# STM.net
KiCad netlist of a schematic drawn in Altium Designer
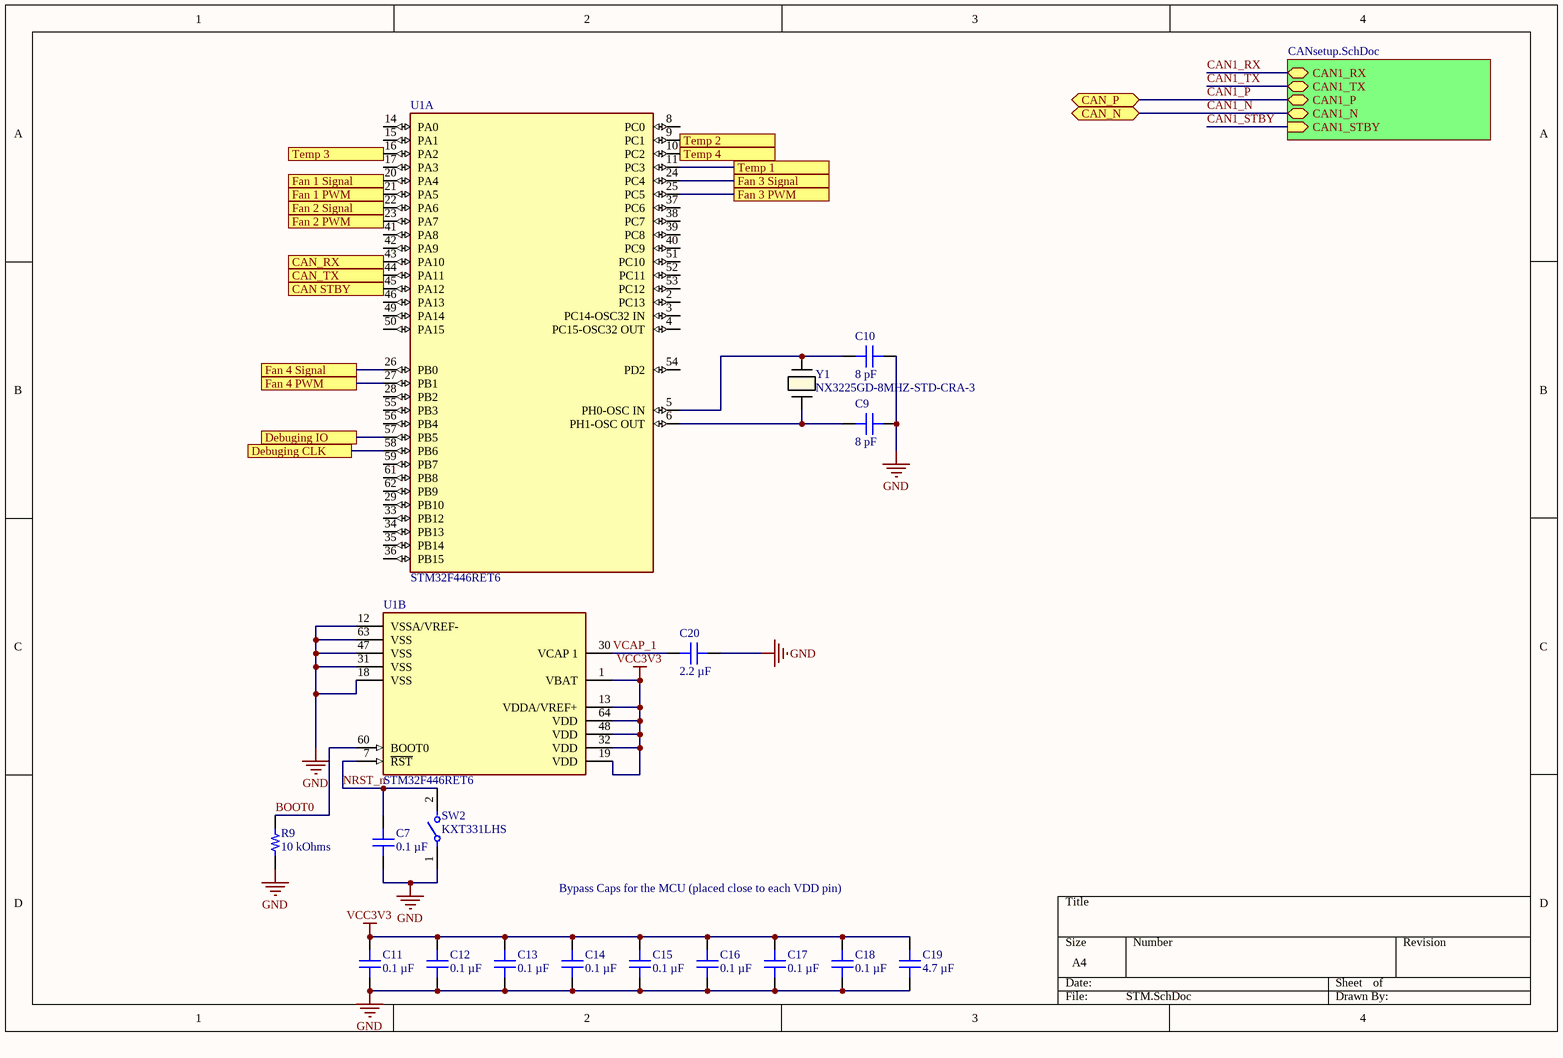
[diagram p0: STM.SchDoc]

(export (version "E")
  (design (tool "Eeschema 10.0.6"))
  (components
    (comp (ref "C7")
      (value "0.1 µF")
      (footprint "CAP 01005_0402")
      (description "CAP CER 0.1UF 6.3V X5R 01005")
      (fields
        (field (name "PART NUMBER") "CL02A104KQ2NNNC")
        (field (name "MANUFACTURER") "Samsung Electro-Mechanics")
      )
      (libsource (lib "Celestial Altium Library - altium_library") (part "Capacitor"))
    )
    (comp (ref "C9")
      (value "8 pF")
      (footprint "CAP 0402_1005")
      (description "CAP CER 8PF 50V C0G/NP0 0402")
      (fields
        (field (name "PART NUMBER") "GCM1555C1H8R0FA16D")
        (field (name "MANUFACTURER") "Murata Electronics")
      )
      (libsource (lib "Celestial Altium Library - altium_library") (part "Capacitor"))
    )
    (comp (ref "C10")
      (value "8 pF")
      (footprint "CAP 0402_1005")
      (description "CAP CER 8PF 50V C0G/NP0 0402")
      (fields
        (field (name "PART NUMBER") "GCM1555C1H8R0FA16D")
        (field (name "MANUFACTURER") "Murata Electronics")
      )
      (libsource (lib "Celestial Altium Library - altium_library") (part "Capacitor"))
    )
    (comp (ref "C11")
      (value "0.1 µF")
      (footprint "CAP 01005_0402")
      (description "CAP CER 0.1UF 6.3V X5R 01005")
      (fields
        (field (name "PART NUMBER") "CL02A104KQ2NNNC")
        (field (name "MANUFACTURER") "Samsung Electro-Mechanics")
      )
      (libsource (lib "Celestial Altium Library - altium_library") (part "Capacitor"))
    )
    (comp (ref "C12")
      (value "0.1 µF")
      (footprint "CAP 01005_0402")
      (description "CAP CER 0.1UF 6.3V X5R 01005")
      (fields
        (field (name "PART NUMBER") "CL02A104KQ2NNNC")
        (field (name "MANUFACTURER") "Samsung Electro-Mechanics")
      )
      (libsource (lib "Celestial Altium Library - altium_library") (part "Capacitor"))
    )
    (comp (ref "C13")
      (value "0.1 µF")
      (footprint "CAP 01005_0402")
      (description "CAP CER 0.1UF 6.3V X5R 01005")
      (fields
        (field (name "PART NUMBER") "CL02A104KQ2NNNC")
        (field (name "MANUFACTURER") "Samsung Electro-Mechanics")
      )
      (libsource (lib "Celestial Altium Library - altium_library") (part "Capacitor"))
    )
    (comp (ref "C14")
      (value "0.1 µF")
      (footprint "CAP 01005_0402")
      (description "CAP CER 0.1UF 6.3V X5R 01005")
      (fields
        (field (name "PART NUMBER") "CL02A104KQ2NNNC")
        (field (name "MANUFACTURER") "Samsung Electro-Mechanics")
      )
      (libsource (lib "Celestial Altium Library - altium_library") (part "Capacitor"))
    )
    (comp (ref "C15")
      (value "0.1 µF")
      (footprint "CAP 01005_0402")
      (description "CAP CER 0.1UF 6.3V X5R 01005")
      (fields
        (field (name "PART NUMBER") "CL02A104KQ2NNNC")
        (field (name "MANUFACTURER") "Samsung Electro-Mechanics")
      )
      (libsource (lib "Celestial Altium Library - altium_library") (part "Capacitor"))
    )
    (comp (ref "C16")
      (value "0.1 µF")
      (footprint "CAP 01005_0402")
      (description "CAP CER 0.1UF 6.3V X5R 01005")
      (fields
        (field (name "PART NUMBER") "CL02A104KQ2NNNC")
        (field (name "MANUFACTURER") "Samsung Electro-Mechanics")
      )
      (libsource (lib "Celestial Altium Library - altium_library") (part "Capacitor"))
    )
    (comp (ref "C17")
      (value "0.1 µF")
      (footprint "CAP 01005_0402")
      (description "CAP CER 0.1UF 6.3V X5R 01005")
      (fields
        (field (name "PART NUMBER") "CL02A104KQ2NNNC")
        (field (name "MANUFACTURER") "Samsung Electro-Mechanics")
      )
      (libsource (lib "Celestial Altium Library - altium_library") (part "Capacitor"))
    )
    (comp (ref "C18")
      (value "0.1 µF")
      (footprint "CAP 01005_0402")
      (description "CAP CER 0.1UF 6.3V X5R 01005")
      (fields
        (field (name "PART NUMBER") "CL02A104KQ2NNNC")
        (field (name "MANUFACTURER") "Samsung Electro-Mechanics")
      )
      (libsource (lib "Celestial Altium Library - altium_library") (part "Capacitor"))
    )
    (comp (ref "C19")
      (value "4.7 µF")
      (footprint "CAP 0402_1005")
      (description "CAP CER 4.7UF 16V X5R 0402")
      (fields
        (field (name "PART NUMBER") "CL05A475MO5NUNC")
        (field (name "MANUFACTURER") "Samsung Electro-Mechanics")
      )
      (libsource (lib "Celestial Altium Library - altium_library") (part "Capacitor"))
    )
    (comp (ref "C20")
      (value "2.2 µF")
      (footprint "CAP 0402_1005")
      (description "CAP CER 2.2UF 16V X5R 0402")
      (fields
        (field (name "PART NUMBER") "CL05A225KO5NQNC")
        (field (name "MANUFACTURER") "Samsung Electro-Mechanics")
      )
      (libsource (lib "Celestial Altium Library - altium_library") (part "Capacitor"))
    )
    (comp (ref "R9")
      (value "10 kOhms")
      (footprint "RES 0201_0603")
      (description "RES SMD 10K OHM 1% 1/20W 0201")
      (fields (field (name "PART NUMBER") "CRCW020110K0FKED") (field (name "MANUFACTURER") "Vishay Dale"))
      (libsource (lib "Celestial Altium Library - altium_library") (part "Resistor"))
    )
    (comp (ref "SW2")
      (value "KXT331LHS")
      (footprint "FP-KXT331LHS-MFG")
      (description "SWITCH TACTILE SPST-NO 0.02A 15V")
      (libsource (lib "Altium Content Vault") (part "bb27bde45df87f1f469753f287ef5ae"))
    )
    (comp (ref "U1")
      (value "STM32F446RET6")
      (footprint "FP-LQFP64-5W-MFG")
      (description "IC MCU 32BIT 512KB FLASH 64LQFP")
      (fields
        (field (name "OCTOPART") "https://octopart.com/stm32f446ret6-stmicroelectronics-52642920")
        (field (name "MANUFACTURER") "ST")
      )
      (libsource (lib "") (part "ee11adc32c0ab33b933cccf4348c338_1"))
    )
    (comp (ref "Y1")
      (value "NX3225GD-8MHZ-STD-CRA-3")
      (footprint "XTAL_NX3225GD-8MHZ-STD-CRA-3_NDK")
      (description "No Description Available")
      (fields (field (name "COPYRIGHT") "Copyright (C) 2024 Ultra Librarian. All rights reserved."))
      (libsource (lib "NX3225GD-8MHZ-STD-CRA-3") (part "NX3225GD-8MHZ-STD-CRA-3"))
    )
  )
  (nets
    (net (code "1") (name "/BOOT0") (class "Default")
      (node (ref "R9") (pin "2") (pinfunction "2_2") (pintype "passive"))
      (node (ref "U1") (pin "60") (pinfunction "BOOT0_60") (pintype "input"))
    )
    (net (code "2") (name "/CAN STBY") (class "Default")
      (node (ref "U1") (pin "45") (pinfunction "PA12_45") (pintype "bidirectional"))
    )
    (net (code "8") (name "/CAN_RX") (class "Default")
      (node (ref "U1") (pin "43") (pinfunction "PA10_43") (pintype "bidirectional"))
    )
    (net (code "9") (name "/CAN_TX") (class "Default")
      (node (ref "U1") (pin "44") (pinfunction "PA11_44") (pintype "bidirectional"))
    )
    (net (code "10") (name "/Debuging CLK") (class "Default")
      (node (ref "U1") (pin "58") (pinfunction "PB6_58") (pintype "bidirectional"))
    )
    (net (code "11") (name "/Debuging IO") (class "Default")
      (node (ref "U1") (pin "57") (pinfunction "PB5_57") (pintype "bidirectional"))
    )
    (net (code "12") (name "/Fan 1 PWM") (class "Default")
      (node (ref "U1") (pin "21") (pinfunction "PA5_21") (pintype "bidirectional"))
    )
    (net (code "13") (name "/Fan 1 Signal") (class "Default")
      (node (ref "U1") (pin "20") (pinfunction "PA4_20") (pintype "bidirectional"))
    )
    (net (code "14") (name "/Fan 2 PWM") (class "Default")
      (node (ref "U1") (pin "23") (pinfunction "PA7_23") (pintype "bidirectional"))
    )
    (net (code "15") (name "/Fan 2 Signal") (class "Default")
      (node (ref "U1") (pin "22") (pinfunction "PA6_22") (pintype "bidirectional"))
    )
    (net (code "16") (name "/Fan 3 PWM") (class "Default")
      (node (ref "U1") (pin "25") (pinfunction "PC5_25") (pintype "bidirectional"))
    )
    (net (code "17") (name "/Fan 3 Signal") (class "Default")
      (node (ref "U1") (pin "24") (pinfunction "PC4_24") (pintype "bidirectional"))
    )
    (net (code "18") (name "/Fan 4 PWM") (class "Default")
      (node (ref "U1") (pin "27") (pinfunction "PB1_27") (pintype "bidirectional"))
    )
    (net (code "19") (name "/Fan 4 Signal") (class "Default")
      (node (ref "U1") (pin "26") (pinfunction "PB0_26") (pintype "bidirectional"))
    )
    (net (code "20") (name "/NRST_n") (class "Default")
      (node (ref "C7") (pin "1") (pinfunction "1_1") (pintype "passive"))
      (node (ref "SW2") (pin "2") (pinfunction "2_2") (pintype "passive"))
      (node (ref "U1") (pin "7") (pinfunction "~{RST}_7") (pintype "input"))
    )
    (net (code "21") (name "/Temp 1") (class "Default")
      (node (ref "U1") (pin "11") (pinfunction "PC3_11") (pintype "bidirectional"))
    )
    (net (code "22") (name "/Temp 2") (class "Default")
      (node (ref "U1") (pin "9") (pinfunction "PC1_9") (pintype "bidirectional"))
    )
    (net (code "23") (name "/Temp 3") (class "Default")
      (node (ref "U1") (pin "16") (pinfunction "PA2_16") (pintype "bidirectional"))
    )
    (net (code "24") (name "/Temp 4") (class "Default")
      (node (ref "U1") (pin "10") (pinfunction "PC2_10") (pintype "bidirectional"))
    )
    (net (code "25") (name "/VCAP_1") (class "Default")
      (node (ref "C20") (pin "2") (pinfunction "2_2") (pintype "passive"))
      (node (ref "U1") (pin "30") (pinfunction "VCAP_1_30") (pintype "power_in"))
    )
    (net (code "26") (name "GND") (class "Default")
      (node (ref "C10") (pin "1") (pinfunction "1_1") (pintype "passive"))
      (node (ref "C11") (pin "2") (pinfunction "2_2") (pintype "passive"))
      (node (ref "C12") (pin "2") (pinfunction "2_2") (pintype "passive"))
      (node (ref "C13") (pin "2") (pinfunction "2_2") (pintype "passive"))
      (node (ref "C14") (pin "2") (pinfunction "2_2") (pintype "passive"))
      (node (ref "C15") (pin "2") (pinfunction "2_2") (pintype "passive"))
      (node (ref "C16") (pin "2") (pinfunction "2_2") (pintype "passive"))
      (node (ref "C17") (pin "2") (pinfunction "2_2") (pintype "passive"))
      (node (ref "C18") (pin "2") (pinfunction "2_2") (pintype "passive"))
      (node (ref "C19") (pin "1") (pinfunction "1_1") (pintype "passive"))
      (node (ref "C20") (pin "1") (pinfunction "1_1") (pintype "passive"))
      (node (ref "C7") (pin "2") (pinfunction "2_2") (pintype "passive"))
      (node (ref "C9") (pin "1") (pinfunction "1_1") (pintype "passive"))
      (node (ref "R9") (pin "1") (pinfunction "1_1") (pintype "passive"))
      (node (ref "SW2") (pin "1") (pinfunction "1_1") (pintype "passive"))
      (node (ref "U1") (pin "12") (pinfunction "VSSA/VREF-_12") (pintype "power_in"))
      (node (ref "U1") (pin "18") (pinfunction "VSS_18") (pintype "power_in"))
      (node (ref "U1") (pin "31") (pinfunction "VSS_31") (pintype "power_in"))
      (node (ref "U1") (pin "47") (pinfunction "VSS_47") (pintype "power_in"))
      (node (ref "U1") (pin "63") (pinfunction "VSS_63") (pintype "power_in"))
    )
    (net (code "27") (name "Net-(U1A-PH0-OSC_IN)") (class "Default")
      (node (ref "C10") (pin "2") (pinfunction "2_2") (pintype "passive"))
      (node (ref "U1") (pin "5") (pinfunction "PH0-OSC_IN_5") (pintype "bidirectional"))
      (node (ref "Y1") (pin "1") (pinfunction "1_1") (pintype "passive"))
    )
    (net (code "28") (name "Net-(U1A-PH1-OSC_OUT)") (class "Default")
      (node (ref "C9") (pin "2") (pinfunction "2_2") (pintype "passive"))
      (node (ref "U1") (pin "6") (pinfunction "PH1-OSC_OUT_6") (pintype "bidirectional"))
      (node (ref "Y1") (pin "2") (pinfunction "2_2") (pintype "passive"))
    )
    (net (code "29") (name "VCC3V3") (class "Default")
      (node (ref "C11") (pin "1") (pinfunction "1_1") (pintype "passive"))
      (node (ref "C12") (pin "1") (pinfunction "1_1") (pintype "passive"))
      (node (ref "C13") (pin "1") (pinfunction "1_1") (pintype "passive"))
      (node (ref "C14") (pin "1") (pinfunction "1_1") (pintype "passive"))
      (node (ref "C15") (pin "1") (pinfunction "1_1") (pintype "passive"))
      (node (ref "C16") (pin "1") (pinfunction "1_1") (pintype "passive"))
      (node (ref "C17") (pin "1") (pinfunction "1_1") (pintype "passive"))
      (node (ref "C18") (pin "1") (pinfunction "1_1") (pintype "passive"))
      (node (ref "C19") (pin "2") (pinfunction "2_2") (pintype "passive"))
      (node (ref "U1") (pin "1") (pinfunction "VBAT_1") (pintype "power_in"))
      (node (ref "U1") (pin "13") (pinfunction "VDDA/VREF+_13") (pintype "power_in"))
      (node (ref "U1") (pin "19") (pinfunction "VDD_19") (pintype "power_in"))
      (node (ref "U1") (pin "32") (pinfunction "VDD_32") (pintype "power_in"))
      (node (ref "U1") (pin "48") (pinfunction "VDD_48") (pintype "power_in"))
      (node (ref "U1") (pin "64") (pinfunction "VDD_64") (pintype "power_in"))
    )
    (net (code "30") (name "unconnected-(U1A-PA0-Pad14)") (class "Default")
      (node (ref "U1") (pin "14") (pinfunction "PA0_14") (pintype "bidirectional"))
    )
    (net (code "31") (name "unconnected-(U1A-PA1-Pad15)") (class "Default")
      (node (ref "U1") (pin "15") (pinfunction "PA1_15") (pintype "bidirectional"))
    )
    (net (code "32") (name "unconnected-(U1A-PA3-Pad17)") (class "Default")
      (node (ref "U1") (pin "17") (pinfunction "PA3_17") (pintype "bidirectional"))
    )
    (net (code "33") (name "unconnected-(U1A-PA8-Pad41)") (class "Default")
      (node (ref "U1") (pin "41") (pinfunction "PA8_41") (pintype "bidirectional"))
    )
    (net (code "34") (name "unconnected-(U1A-PA9-Pad42)") (class "Default")
      (node (ref "U1") (pin "42") (pinfunction "PA9_42") (pintype "bidirectional"))
    )
    (net (code "35") (name "unconnected-(U1A-PA13-Pad46)") (class "Default")
      (node (ref "U1") (pin "46") (pinfunction "PA13_46") (pintype "bidirectional"))
    )
    (net (code "36") (name "unconnected-(U1A-PA14-Pad49)") (class "Default")
      (node (ref "U1") (pin "49") (pinfunction "PA14_49") (pintype "bidirectional"))
    )
    (net (code "37") (name "unconnected-(U1A-PA15-Pad50)") (class "Default")
      (node (ref "U1") (pin "50") (pinfunction "PA15_50") (pintype "bidirectional"))
    )
    (net (code "38") (name "unconnected-(U1A-PB2-Pad28)") (class "Default")
      (node (ref "U1") (pin "28") (pinfunction "PB2_28") (pintype "bidirectional"))
    )
    (net (code "39") (name "unconnected-(U1A-PB3-Pad55)") (class "Default")
      (node (ref "U1") (pin "55") (pinfunction "PB3_55") (pintype "bidirectional"))
    )
    (net (code "40") (name "unconnected-(U1A-PB4-Pad56)") (class "Default")
      (node (ref "U1") (pin "56") (pinfunction "PB4_56") (pintype "bidirectional"))
    )
    (net (code "41") (name "unconnected-(U1A-PB7-Pad59)") (class "Default")
      (node (ref "U1") (pin "59") (pinfunction "PB7_59") (pintype "bidirectional"))
    )
    (net (code "42") (name "unconnected-(U1A-PB8-Pad61)") (class "Default")
      (node (ref "U1") (pin "61") (pinfunction "PB8_61") (pintype "bidirectional"))
    )
    (net (code "43") (name "unconnected-(U1A-PB9-Pad62)") (class "Default")
      (node (ref "U1") (pin "62") (pinfunction "PB9_62") (pintype "bidirectional"))
    )
    (net (code "44") (name "unconnected-(U1A-PB10-Pad29)") (class "Default")
      (node (ref "U1") (pin "29") (pinfunction "PB10_29") (pintype "bidirectional"))
    )
    (net (code "45") (name "unconnected-(U1A-PB12-Pad33)") (class "Default")
      (node (ref "U1") (pin "33") (pinfunction "PB12_33") (pintype "bidirectional"))
    )
    (net (code "46") (name "unconnected-(U1A-PB13-Pad34)") (class "Default")
      (node (ref "U1") (pin "34") (pinfunction "PB13_34") (pintype "bidirectional"))
    )
    (net (code "47") (name "unconnected-(U1A-PB14-Pad35)") (class "Default")
      (node (ref "U1") (pin "35") (pinfunction "PB14_35") (pintype "bidirectional"))
    )
    (net (code "48") (name "unconnected-(U1A-PB15-Pad36)") (class "Default")
      (node (ref "U1") (pin "36") (pinfunction "PB15_36") (pintype "bidirectional"))
    )
    (net (code "49") (name "unconnected-(U1A-PC0-Pad8)") (class "Default")
      (node (ref "U1") (pin "8") (pinfunction "PC0_8") (pintype "bidirectional"))
    )
    (net (code "50") (name "unconnected-(U1A-PC6-Pad37)") (class "Default")
      (node (ref "U1") (pin "37") (pinfunction "PC6_37") (pintype "bidirectional"))
    )
    (net (code "51") (name "unconnected-(U1A-PC7-Pad38)") (class "Default")
      (node (ref "U1") (pin "38") (pinfunction "PC7_38") (pintype "bidirectional"))
    )
    (net (code "52") (name "unconnected-(U1A-PC8-Pad39)") (class "Default")
      (node (ref "U1") (pin "39") (pinfunction "PC8_39") (pintype "bidirectional"))
    )
    (net (code "53") (name "unconnected-(U1A-PC9-Pad40)") (class "Default")
      (node (ref "U1") (pin "40") (pinfunction "PC9_40") (pintype "bidirectional"))
    )
    (net (code "54") (name "unconnected-(U1A-PC10-Pad51)") (class "Default")
      (node (ref "U1") (pin "51") (pinfunction "PC10_51") (pintype "bidirectional"))
    )
    (net (code "55") (name "unconnected-(U1A-PC11-Pad52)") (class "Default")
      (node (ref "U1") (pin "52") (pinfunction "PC11_52") (pintype "bidirectional"))
    )
    (net (code "56") (name "unconnected-(U1A-PC12-Pad53)") (class "Default")
      (node (ref "U1") (pin "53") (pinfunction "PC12_53") (pintype "bidirectional"))
    )
    (net (code "57") (name "unconnected-(U1A-PC13-Pad2)") (class "Default")
      (node (ref "U1") (pin "2") (pinfunction "PC13_2") (pintype "bidirectional"))
    )
    (net (code "58") (name "unconnected-(U1A-PC14-OSC32_IN-Pad3)") (class "Default")
      (node (ref "U1") (pin "3") (pinfunction "PC14-OSC32_IN_3") (pintype "bidirectional"))
    )
    (net (code "59") (name "unconnected-(U1A-PC15-OSC32_OUT-Pad4)") (class "Default")
      (node (ref "U1") (pin "4") (pinfunction "PC15-OSC32_OUT_4") (pintype "bidirectional"))
    )
    (net (code "60") (name "unconnected-(U1A-PD2-Pad54)") (class "Default")
      (node (ref "U1") (pin "54") (pinfunction "PD2_54") (pintype "bidirectional"))
    )
  )
)
